# QSPI.net
KiCad netlist of a schematic drawn in Altium Designer
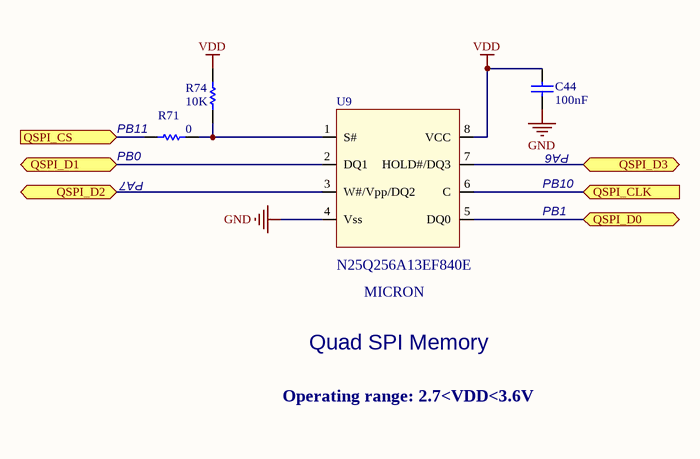
[diagram p0: QSPI.SchDoc]

(export (version "E")
  (design (tool "Eeschema 10.0.6"))
  (components
    (comp (ref "C44")
      (value "100nF")
      (footprint "0402C")
      (description "Capacitor")
      (fields (field (name "PUBLISHER") "Altium Limited"))
      (libsource (lib "Miscellaneous Devices") (part "Cap"))
    )
    (comp (ref "R71")
      (value "0")
      (footprint "0603R")
      (description "Resistor")
      (fields (field (name "PUBLISHER") "Altium Limited"))
      (libsource (lib "Miscellaneous Devices") (part "Res1"))
    )
    (comp (ref "R74")
      (value "10K")
      (footprint "0402R")
      (description "Resistor")
      (fields (field (name "PUBLISHER") "Altium Limited"))
      (libsource (lib "Miscellaneous Devices") (part "res1"))
    )
    (comp (ref "U9")
      (value "N25Q256A13EF840E")
      (footprint "DFN8_1R27_6X8_TP4R8X5R8")
      (libsource (lib "MB1144_2") (part "QSPI_8pins"))
    )
  )
  (nets
    (net (code "1") (name "/QSPI_CLK") (class "Default")
      (node (ref "U9") (pin "6") (pinfunction "C_6") (pintype "passive"))
    )
    (net (code "2") (name "/QSPI_CS") (class "Default")
      (node (ref "R71") (pin "2") (pinfunction "2_2") (pintype "passive"))
    )
    (net (code "3") (name "/QSPI_D0") (class "Default")
      (node (ref "U9") (pin "5") (pinfunction "DQ0_5") (pintype "passive"))
    )
    (net (code "4") (name "/QSPI_D1") (class "Default")
      (node (ref "U9") (pin "2") (pinfunction "DQ1_2") (pintype "passive"))
    )
    (net (code "5") (name "/QSPI_D2") (class "Default")
      (node (ref "U9") (pin "3") (pinfunction "W#/Vpp/DQ2_3") (pintype "passive"))
    )
    (net (code "6") (name "/QSPI_D3") (class "Default")
      (node (ref "U9") (pin "7") (pinfunction "HOLD#/DQ3_7") (pintype "passive"))
    )
    (net (code "7") (name "GND") (class "Default")
      (node (ref "C44") (pin "2") (pinfunction "2_2") (pintype "passive"))
      (node (ref "U9") (pin "4") (pinfunction "Vss_4") (pintype "passive"))
    )
    (net (code "8") (name "Net-(U9-S#)") (class "Default")
      (node (ref "R71") (pin "1") (pinfunction "1_1") (pintype "passive"))
      (node (ref "R74") (pin "2") (pinfunction "2_2") (pintype "passive"))
      (node (ref "U9") (pin "1") (pinfunction "S#_1") (pintype "passive"))
    )
    (net (code "9") (name "VDD") (class "Default")
      (node (ref "C44") (pin "1") (pinfunction "1_1") (pintype "passive"))
      (node (ref "R74") (pin "1") (pinfunction "1_1") (pintype "passive"))
      (node (ref "U9") (pin "8") (pinfunction "VCC_8") (pintype "passive"))
    )
  )
)
